# pwm_bot_sheild.net
KiCad netlist of a schematic drawn in Altium Designer
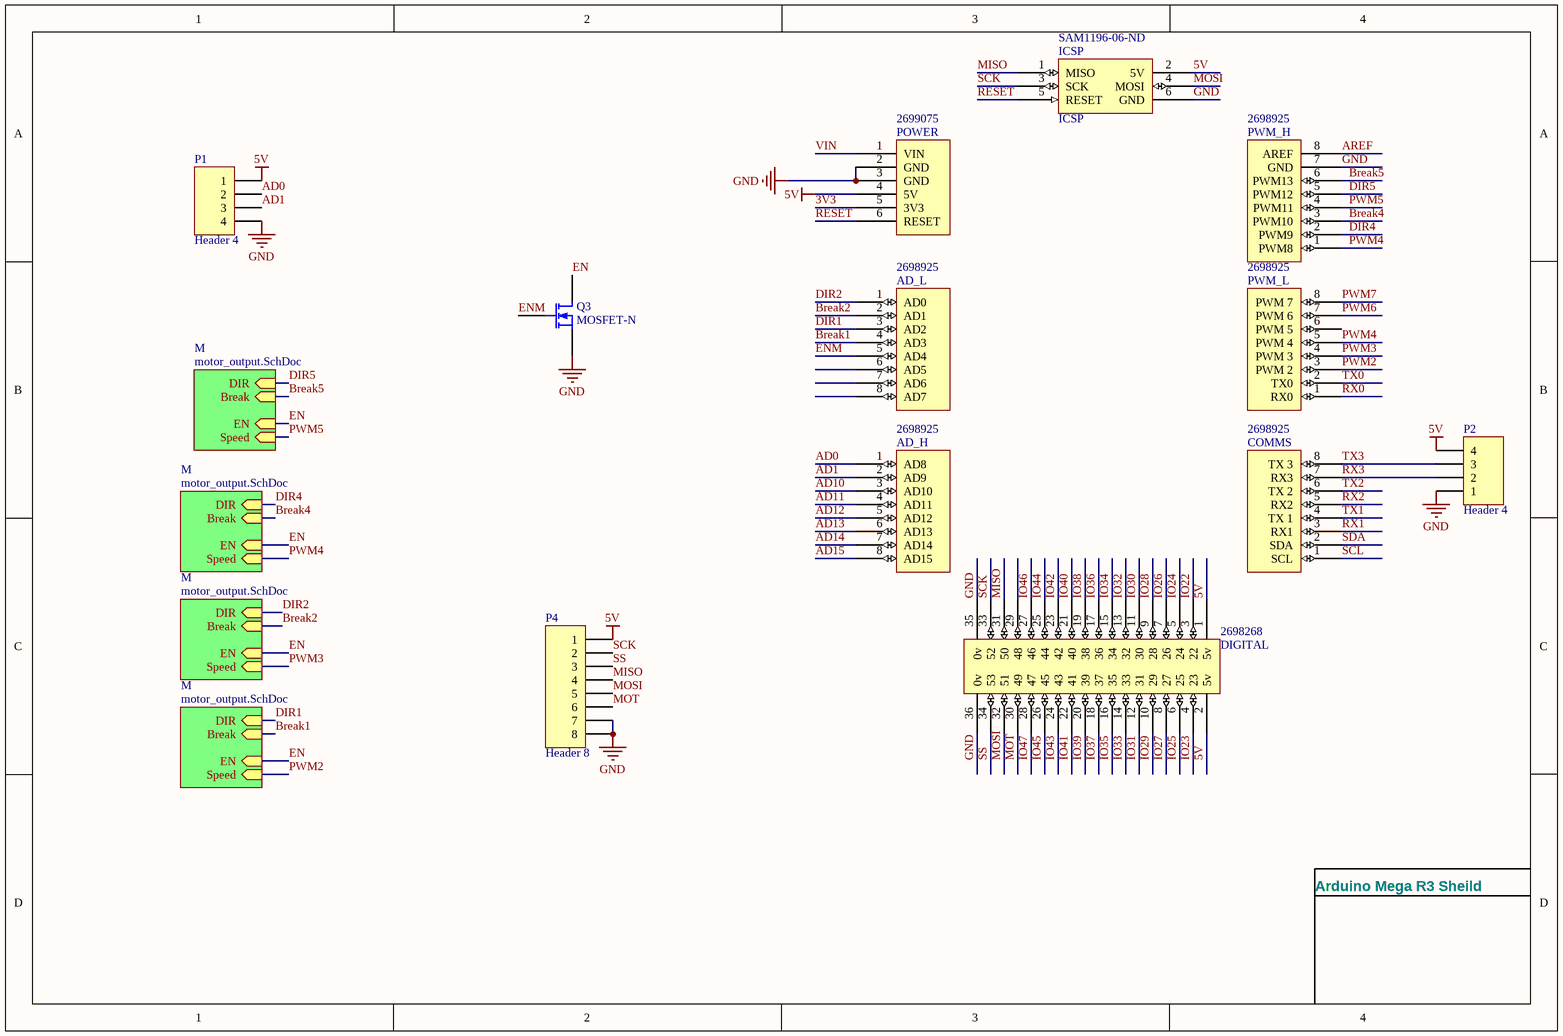
[diagram p0: pwm_bot_sheild.SchDoc]

(export (version "E")
  (design (tool "Eeschema 10.0.6"))
  (components
    (comp (ref "AD_H")
      (value "AD_H")
      (footprint "Header 8x1 8.5mm")
      (fields (field (name "SUPPLIER PART NUMBER 4") "2698925"))
      (libsource (lib "Header") (part "AD_H"))
    )
    (comp (ref "AD_L")
      (value "AD_L")
      (footprint "Header 8x1 8.5mm")
      (fields (field (name "SUPPLIER PART NUMBER 5") "2698925"))
      (libsource (lib "Header") (part "AD_L"))
    )
    (comp (ref "COMMS")
      (value "Communication")
      (footprint "Header 8x1 8.5mm")
      (fields (field (name "SUPPLIER PART NUMBER 4") "2698925"))
      (libsource (lib "Header") (part "Communication"))
    )
    (comp (ref "DIGITAL")
      (value "IO_36")
      (footprint "HEADER 36X 8MM")
      (fields (field (name "SUPPLIER PART NUMBER 5") "2698268"))
      (libsource (lib "Header") (part "IO_36"))
    )
    (comp (ref "ICSP")
      (value "ICSP")
      (footprint "ICSP")
      (fields (field (name "SUPPLIER PART NUMBER 5") "SAM1196-06-ND"))
      (libsource (lib "Header") (part "ICSP"))
    )
    (comp (ref "P1")
      (value "Header 4")
      (footprint "B4B-XH-A")
      (description "Header, 4-Pin")
      (fields (field (name "PUBLISHER") "Altium Limited"))
      (libsource (lib "") (part "Header 4_1"))
    )
    (comp (ref "P2")
      (value "Header 4")
      (footprint "B4B-XH-A")
      (description "Header, 4-Pin")
      (fields (field (name "PUBLISHER") "Altium Limited"))
      (libsource (lib "Miscellaneous Connectors") (part "Header 4"))
    )
    (comp (ref "P4")
      (value "Header 8")
      (footprint "B8B-XH-A")
      (description "Header, 8-Pin")
      (fields (field (name "PUBLISHER") "Altium Limited"))
      (libsource (lib "Miscellaneous Connectors") (part "Header 8"))
    )
    (comp (ref "POWER")
      (value "POWER")
      (footprint "Header 6x1 8.5mm")
      (fields (field (name "SUPPLIER PART NUMBER 2") "2699075"))
      (libsource (lib "Header") (part "POWER"))
    )
    (comp (ref "PWM_H")
      (value "PWM_H")
      (footprint "Header 8x1 8.5mm")
      (fields (field (name "SUPPLIER PART NUMBER 4") "2698925"))
      (libsource (lib "Header") (part "PWM_H"))
    )
    (comp (ref "PWM_L")
      (value "PWM_L")
      (footprint "Header 8x1 8.5mm")
      (fields (field (name "SUPPLIER PART NUMBER 4") "2698925"))
      (libsource (lib "Header") (part "PWM_L"))
    )
    (comp (ref "Q3")
      (value "MOSFET-N")
      (footprint "Tranny")
      (description "N-Channel MOSFET")
      (fields (field (name "PUBLISHER") "Altium Limited"))
      (libsource (lib "Miscellaneous Devices") (part "MOSFET-N"))
    )
  )
  (nets
    (net (code "1") (name "/3V3") (class "Default")
      (node (ref "POWER") (pin "5") (pinfunction "3V3_5") (pintype "power_in"))
    )
    (net (code "2") (name "/AD0") (class "Default")
      (node (ref "AD_H") (pin "1") (pinfunction "AD8_1") (pintype "bidirectional"))
      (node (ref "P1") (pin "2") (pinfunction "2_2") (pintype "passive"))
    )
    (net (code "3") (name "/AD1") (class "Default")
      (node (ref "AD_H") (pin "2") (pinfunction "AD9_2") (pintype "bidirectional"))
      (node (ref "P1") (pin "3") (pinfunction "3_3") (pintype "passive"))
    )
    (net (code "4") (name "/AD10") (class "Default")
      (node (ref "AD_H") (pin "3") (pinfunction "AD10_3") (pintype "bidirectional"))
    )
    (net (code "5") (name "/AD11") (class "Default")
      (node (ref "AD_H") (pin "4") (pinfunction "AD11_4") (pintype "bidirectional"))
    )
    (net (code "6") (name "/AD12") (class "Default")
      (node (ref "AD_H") (pin "5") (pinfunction "AD12_5") (pintype "bidirectional"))
    )
    (net (code "7") (name "/AD13") (class "Default")
      (node (ref "AD_H") (pin "6") (pinfunction "AD13_6") (pintype "bidirectional"))
    )
    (net (code "8") (name "/AD14") (class "Default")
      (node (ref "AD_H") (pin "7") (pinfunction "AD14_7") (pintype "bidirectional"))
    )
    (net (code "9") (name "/AD15") (class "Default")
      (node (ref "AD_H") (pin "8") (pinfunction "AD15_8") (pintype "bidirectional"))
    )
    (net (code "10") (name "/AREF") (class "Default")
      (node (ref "PWM_H") (pin "8") (pinfunction "AREF_8") (pintype "passive"))
    )
    (net (code "11") (name "/Break1") (class "Default")
      (node (ref "AD_L") (pin "4") (pinfunction "AD3_4") (pintype "bidirectional"))
    )
    (net (code "12") (name "/Break2") (class "Default")
      (node (ref "AD_L") (pin "2") (pinfunction "AD1_2") (pintype "bidirectional"))
    )
    (net (code "13") (name "/Break4") (class "Default")
      (node (ref "PWM_H") (pin "3") (pinfunction "PWM10_3") (pintype "bidirectional"))
    )
    (net (code "14") (name "/Break5") (class "Default")
      (node (ref "PWM_H") (pin "6") (pinfunction "PWM13_6") (pintype "bidirectional"))
    )
    (net (code "15") (name "/DIR1") (class "Default")
      (node (ref "AD_L") (pin "3") (pinfunction "AD2_3") (pintype "bidirectional"))
    )
    (net (code "16") (name "/DIR2") (class "Default")
      (node (ref "AD_L") (pin "1") (pinfunction "AD0_1") (pintype "bidirectional"))
    )
    (net (code "17") (name "/DIR4") (class "Default")
      (node (ref "PWM_H") (pin "2") (pinfunction "PWM9_2") (pintype "bidirectional"))
    )
    (net (code "18") (name "/DIR5") (class "Default")
      (node (ref "PWM_H") (pin "5") (pinfunction "PWM12_5") (pintype "bidirectional"))
    )
    (net (code "19") (name "/EN") (class "Default")
      (node (ref "Q3") (pin "1") (pinfunction "D_1") (pintype "passive"))
    )
    (net (code "20") (name "/ENM") (class "Default")
      (node (ref "AD_L") (pin "5") (pinfunction "AD4_5") (pintype "bidirectional"))
      (node (ref "Q3") (pin "2") (pinfunction "G_2") (pintype "passive"))
    )
    (net (code "21") (name "/IO22") (class "Default")
      (node (ref "DIGITAL") (pin "3") (pinfunction "22_3") (pintype "bidirectional"))
    )
    (net (code "22") (name "/IO23") (class "Default")
      (node (ref "DIGITAL") (pin "4") (pinfunction "23_4") (pintype "bidirectional"))
    )
    (net (code "23") (name "/IO24") (class "Default")
      (node (ref "DIGITAL") (pin "5") (pinfunction "24_5") (pintype "bidirectional"))
    )
    (net (code "24") (name "/IO25") (class "Default")
      (node (ref "DIGITAL") (pin "6") (pinfunction "25_6") (pintype "bidirectional"))
    )
    (net (code "25") (name "/IO26") (class "Default")
      (node (ref "DIGITAL") (pin "7") (pinfunction "26_7") (pintype "bidirectional"))
    )
    (net (code "26") (name "/IO27") (class "Default")
      (node (ref "DIGITAL") (pin "8") (pinfunction "27_8") (pintype "bidirectional"))
    )
    (net (code "27") (name "/IO28") (class "Default")
      (node (ref "DIGITAL") (pin "9") (pinfunction "28_9") (pintype "bidirectional"))
    )
    (net (code "28") (name "/IO29") (class "Default")
      (node (ref "DIGITAL") (pin "10") (pinfunction "29_10") (pintype "bidirectional"))
    )
    (net (code "29") (name "/IO30") (class "Default")
      (node (ref "DIGITAL") (pin "11") (pinfunction "30_11") (pintype "bidirectional"))
    )
    (net (code "30") (name "/IO31") (class "Default")
      (node (ref "DIGITAL") (pin "12") (pinfunction "31_12") (pintype "bidirectional"))
    )
    (net (code "31") (name "/IO32") (class "Default")
      (node (ref "DIGITAL") (pin "13") (pinfunction "32_13") (pintype "bidirectional"))
    )
    (net (code "32") (name "/IO33") (class "Default")
      (node (ref "DIGITAL") (pin "14") (pinfunction "33_14") (pintype "bidirectional"))
    )
    (net (code "33") (name "/IO34") (class "Default")
      (node (ref "DIGITAL") (pin "15") (pinfunction "34_15") (pintype "bidirectional"))
    )
    (net (code "34") (name "/IO35") (class "Default")
      (node (ref "DIGITAL") (pin "16") (pinfunction "35_16") (pintype "bidirectional"))
    )
    (net (code "35") (name "/IO36") (class "Default")
      (node (ref "DIGITAL") (pin "17") (pinfunction "36_17") (pintype "bidirectional"))
    )
    (net (code "36") (name "/IO37") (class "Default")
      (node (ref "DIGITAL") (pin "18") (pinfunction "37_18") (pintype "bidirectional"))
    )
    (net (code "37") (name "/IO38") (class "Default")
      (node (ref "DIGITAL") (pin "19") (pinfunction "38_19") (pintype "bidirectional"))
    )
    (net (code "38") (name "/IO39") (class "Default")
      (node (ref "DIGITAL") (pin "20") (pinfunction "39_20") (pintype "bidirectional"))
    )
    (net (code "39") (name "/IO40") (class "Default")
      (node (ref "DIGITAL") (pin "21") (pinfunction "40_21") (pintype "bidirectional"))
    )
    (net (code "40") (name "/IO41") (class "Default")
      (node (ref "DIGITAL") (pin "22") (pinfunction "41_22") (pintype "bidirectional"))
    )
    (net (code "41") (name "/IO42") (class "Default")
      (node (ref "DIGITAL") (pin "23") (pinfunction "42_23") (pintype "bidirectional"))
    )
    (net (code "42") (name "/IO43") (class "Default")
      (node (ref "DIGITAL") (pin "24") (pinfunction "43_24") (pintype "bidirectional"))
    )
    (net (code "43") (name "/IO44") (class "Default")
      (node (ref "DIGITAL") (pin "25") (pinfunction "44_25") (pintype "bidirectional"))
    )
    (net (code "44") (name "/IO45") (class "Default")
      (node (ref "DIGITAL") (pin "26") (pinfunction "45_26") (pintype "bidirectional"))
    )
    (net (code "45") (name "/IO46") (class "Default")
      (node (ref "DIGITAL") (pin "27") (pinfunction "46_27") (pintype "bidirectional"))
    )
    (net (code "46") (name "/IO47") (class "Default")
      (node (ref "DIGITAL") (pin "28") (pinfunction "47_28") (pintype "bidirectional"))
    )
    (net (code "47") (name "/MISO") (class "Default")
      (node (ref "DIGITAL") (pin "31") (pinfunction "50_31") (pintype "bidirectional"))
      (node (ref "ICSP") (pin "1") (pinfunction "MISO_1") (pintype "bidirectional"))
      (node (ref "P4") (pin "4") (pinfunction "4_4") (pintype "passive"))
    )
    (net (code "48") (name "/MOSI") (class "Default")
      (node (ref "DIGITAL") (pin "32") (pinfunction "51_32") (pintype "bidirectional"))
      (node (ref "ICSP") (pin "4") (pinfunction "MOSI_4") (pintype "bidirectional"))
      (node (ref "P4") (pin "5") (pinfunction "5_5") (pintype "passive"))
    )
    (net (code "49") (name "/MOT") (class "Default")
      (node (ref "DIGITAL") (pin "30") (pinfunction "49_30") (pintype "bidirectional"))
      (node (ref "P4") (pin "6") (pinfunction "6_6") (pintype "passive"))
    )
    (net (code "50") (name "/PWM2") (class "Default")
      (node (ref "PWM_L") (pin "3") (pinfunction "PWM_2_3") (pintype "bidirectional"))
    )
    (net (code "51") (name "/PWM3") (class "Default")
      (node (ref "PWM_L") (pin "4") (pinfunction "PWM_3_4") (pintype "bidirectional"))
    )
    (net (code "52") (name "/PWM4") (class "Default")
      (node (ref "PWM_H") (pin "1") (pinfunction "PWM8_1") (pintype "bidirectional"))
      (node (ref "PWM_L") (pin "5") (pinfunction "PWM_4_5") (pintype "bidirectional"))
    )
    (net (code "53") (name "/PWM5") (class "Default")
      (node (ref "PWM_H") (pin "4") (pinfunction "PWM11_4") (pintype "bidirectional"))
    )
    (net (code "54") (name "/PWM6") (class "Default")
      (node (ref "PWM_L") (pin "7") (pinfunction "PWM_6_7") (pintype "bidirectional"))
    )
    (net (code "55") (name "/PWM7") (class "Default")
      (node (ref "PWM_L") (pin "8") (pinfunction "PWM_7_8") (pintype "bidirectional"))
    )
    (net (code "56") (name "/RESET") (class "Default")
      (node (ref "ICSP") (pin "5") (pinfunction "RESET_5") (pintype "input"))
      (node (ref "POWER") (pin "6") (pinfunction "RESET_6") (pintype "passive"))
    )
    (net (code "57") (name "/RX0") (class "Default")
      (node (ref "PWM_L") (pin "1") (pinfunction "RX0_1") (pintype "bidirectional"))
    )
    (net (code "58") (name "/RX1") (class "Default")
      (node (ref "COMMS") (pin "3") (pinfunction "RX1_3") (pintype "bidirectional"))
    )
    (net (code "59") (name "/RX2") (class "Default")
      (node (ref "COMMS") (pin "5") (pinfunction "RX2_5") (pintype "bidirectional"))
    )
    (net (code "60") (name "/RX3") (class "Default")
      (node (ref "COMMS") (pin "7") (pinfunction "RX3_7") (pintype "bidirectional"))
      (node (ref "P2") (pin "2") (pinfunction "2_2") (pintype "passive"))
    )
    (net (code "61") (name "/SCK") (class "Default")
      (node (ref "DIGITAL") (pin "33") (pinfunction "52_33") (pintype "bidirectional"))
      (node (ref "ICSP") (pin "3") (pinfunction "SCK_3") (pintype "bidirectional"))
      (node (ref "P4") (pin "2") (pinfunction "2_2") (pintype "passive"))
    )
    (net (code "62") (name "/SCL") (class "Default")
      (node (ref "COMMS") (pin "1") (pinfunction "SCL_1") (pintype "bidirectional"))
    )
    (net (code "63") (name "/SDA") (class "Default")
      (node (ref "COMMS") (pin "2") (pinfunction "SDA_2") (pintype "bidirectional"))
    )
    (net (code "64") (name "/SS") (class "Default")
      (node (ref "DIGITAL") (pin "34") (pinfunction "53_34") (pintype "bidirectional"))
      (node (ref "P4") (pin "3") (pinfunction "3_3") (pintype "passive"))
    )
    (net (code "65") (name "/TX0") (class "Default")
      (node (ref "PWM_L") (pin "2") (pinfunction "TX0_2") (pintype "bidirectional"))
    )
    (net (code "66") (name "/TX1") (class "Default")
      (node (ref "COMMS") (pin "4") (pinfunction "TX_1_4") (pintype "bidirectional"))
    )
    (net (code "67") (name "/TX2") (class "Default")
      (node (ref "COMMS") (pin "6") (pinfunction "TX_2_6") (pintype "bidirectional"))
    )
    (net (code "68") (name "/TX3") (class "Default")
      (node (ref "COMMS") (pin "8") (pinfunction "TX_3_8") (pintype "bidirectional"))
      (node (ref "P2") (pin "3") (pinfunction "3_3") (pintype "passive"))
    )
    (net (code "69") (name "/VIN") (class "Default")
      (node (ref "POWER") (pin "1") (pinfunction "VIN_1") (pintype "power_in"))
    )
    (net (code "70") (name "5V") (class "Default")
      (node (ref "DIGITAL") (pin "1") (pinfunction "5v_1") (pintype "power_in"))
      (node (ref "DIGITAL") (pin "2") (pinfunction "5v_2") (pintype "power_in"))
      (node (ref "ICSP") (pin "2") (pinfunction "5V_2") (pintype "power_in"))
      (node (ref "P1") (pin "1") (pinfunction "1_1") (pintype "passive"))
      (node (ref "P2") (pin "4") (pinfunction "4_4") (pintype "passive"))
      (node (ref "P4") (pin "1") (pinfunction "1_1") (pintype "passive"))
      (node (ref "POWER") (pin "4") (pinfunction "5V_4") (pintype "power_in"))
    )
    (net (code "71") (name "GND") (class "Default")
      (node (ref "DIGITAL") (pin "35") (pinfunction "0v_35") (pintype "power_in"))
      (node (ref "DIGITAL") (pin "36") (pinfunction "0v_36") (pintype "power_in"))
      (node (ref "ICSP") (pin "6") (pinfunction "GND_6") (pintype "power_in"))
      (node (ref "P1") (pin "4") (pinfunction "4_4") (pintype "passive"))
      (node (ref "P2") (pin "1") (pinfunction "1_1") (pintype "passive"))
      (node (ref "P4") (pin "7") (pinfunction "7_7") (pintype "passive"))
      (node (ref "P4") (pin "8") (pinfunction "8_8") (pintype "passive"))
      (node (ref "POWER") (pin "2") (pinfunction "GND_2") (pintype "power_in"))
      (node (ref "POWER") (pin "3") (pinfunction "GND_3") (pintype "power_in"))
      (node (ref "PWM_H") (pin "7") (pinfunction "GND_7") (pintype "power_in"))
      (node (ref "Q3") (pin "3") (pinfunction "S_3") (pintype "passive"))
    )
    (net (code "72") (name "unconnected-(AD_L-AD5-Pad6)") (class "Default")
      (node (ref "AD_L") (pin "6") (pinfunction "AD5_6") (pintype "bidirectional"))
    )
    (net (code "73") (name "unconnected-(AD_L-AD6-Pad7)") (class "Default")
      (node (ref "AD_L") (pin "7") (pinfunction "AD6_7") (pintype "bidirectional"))
    )
    (net (code "74") (name "unconnected-(AD_L-AD7-Pad8)") (class "Default")
      (node (ref "AD_L") (pin "8") (pinfunction "AD7_8") (pintype "bidirectional"))
    )
    (net (code "75") (name "unconnected-(DIGITAL-48-Pad29)") (class "Default")
      (node (ref "DIGITAL") (pin "29") (pinfunction "48_29") (pintype "bidirectional"))
    )
    (net (code "76") (name "unconnected-(PWM_L-PWM_5-Pad6)") (class "Default")
      (node (ref "PWM_L") (pin "6") (pinfunction "PWM_5_6") (pintype "bidirectional"))
    )
  )
)
